# SCH_Cupcake-Hacker-Card_2025-04-10.net
KiCad netlist of a schematic drawn in EasyEDA
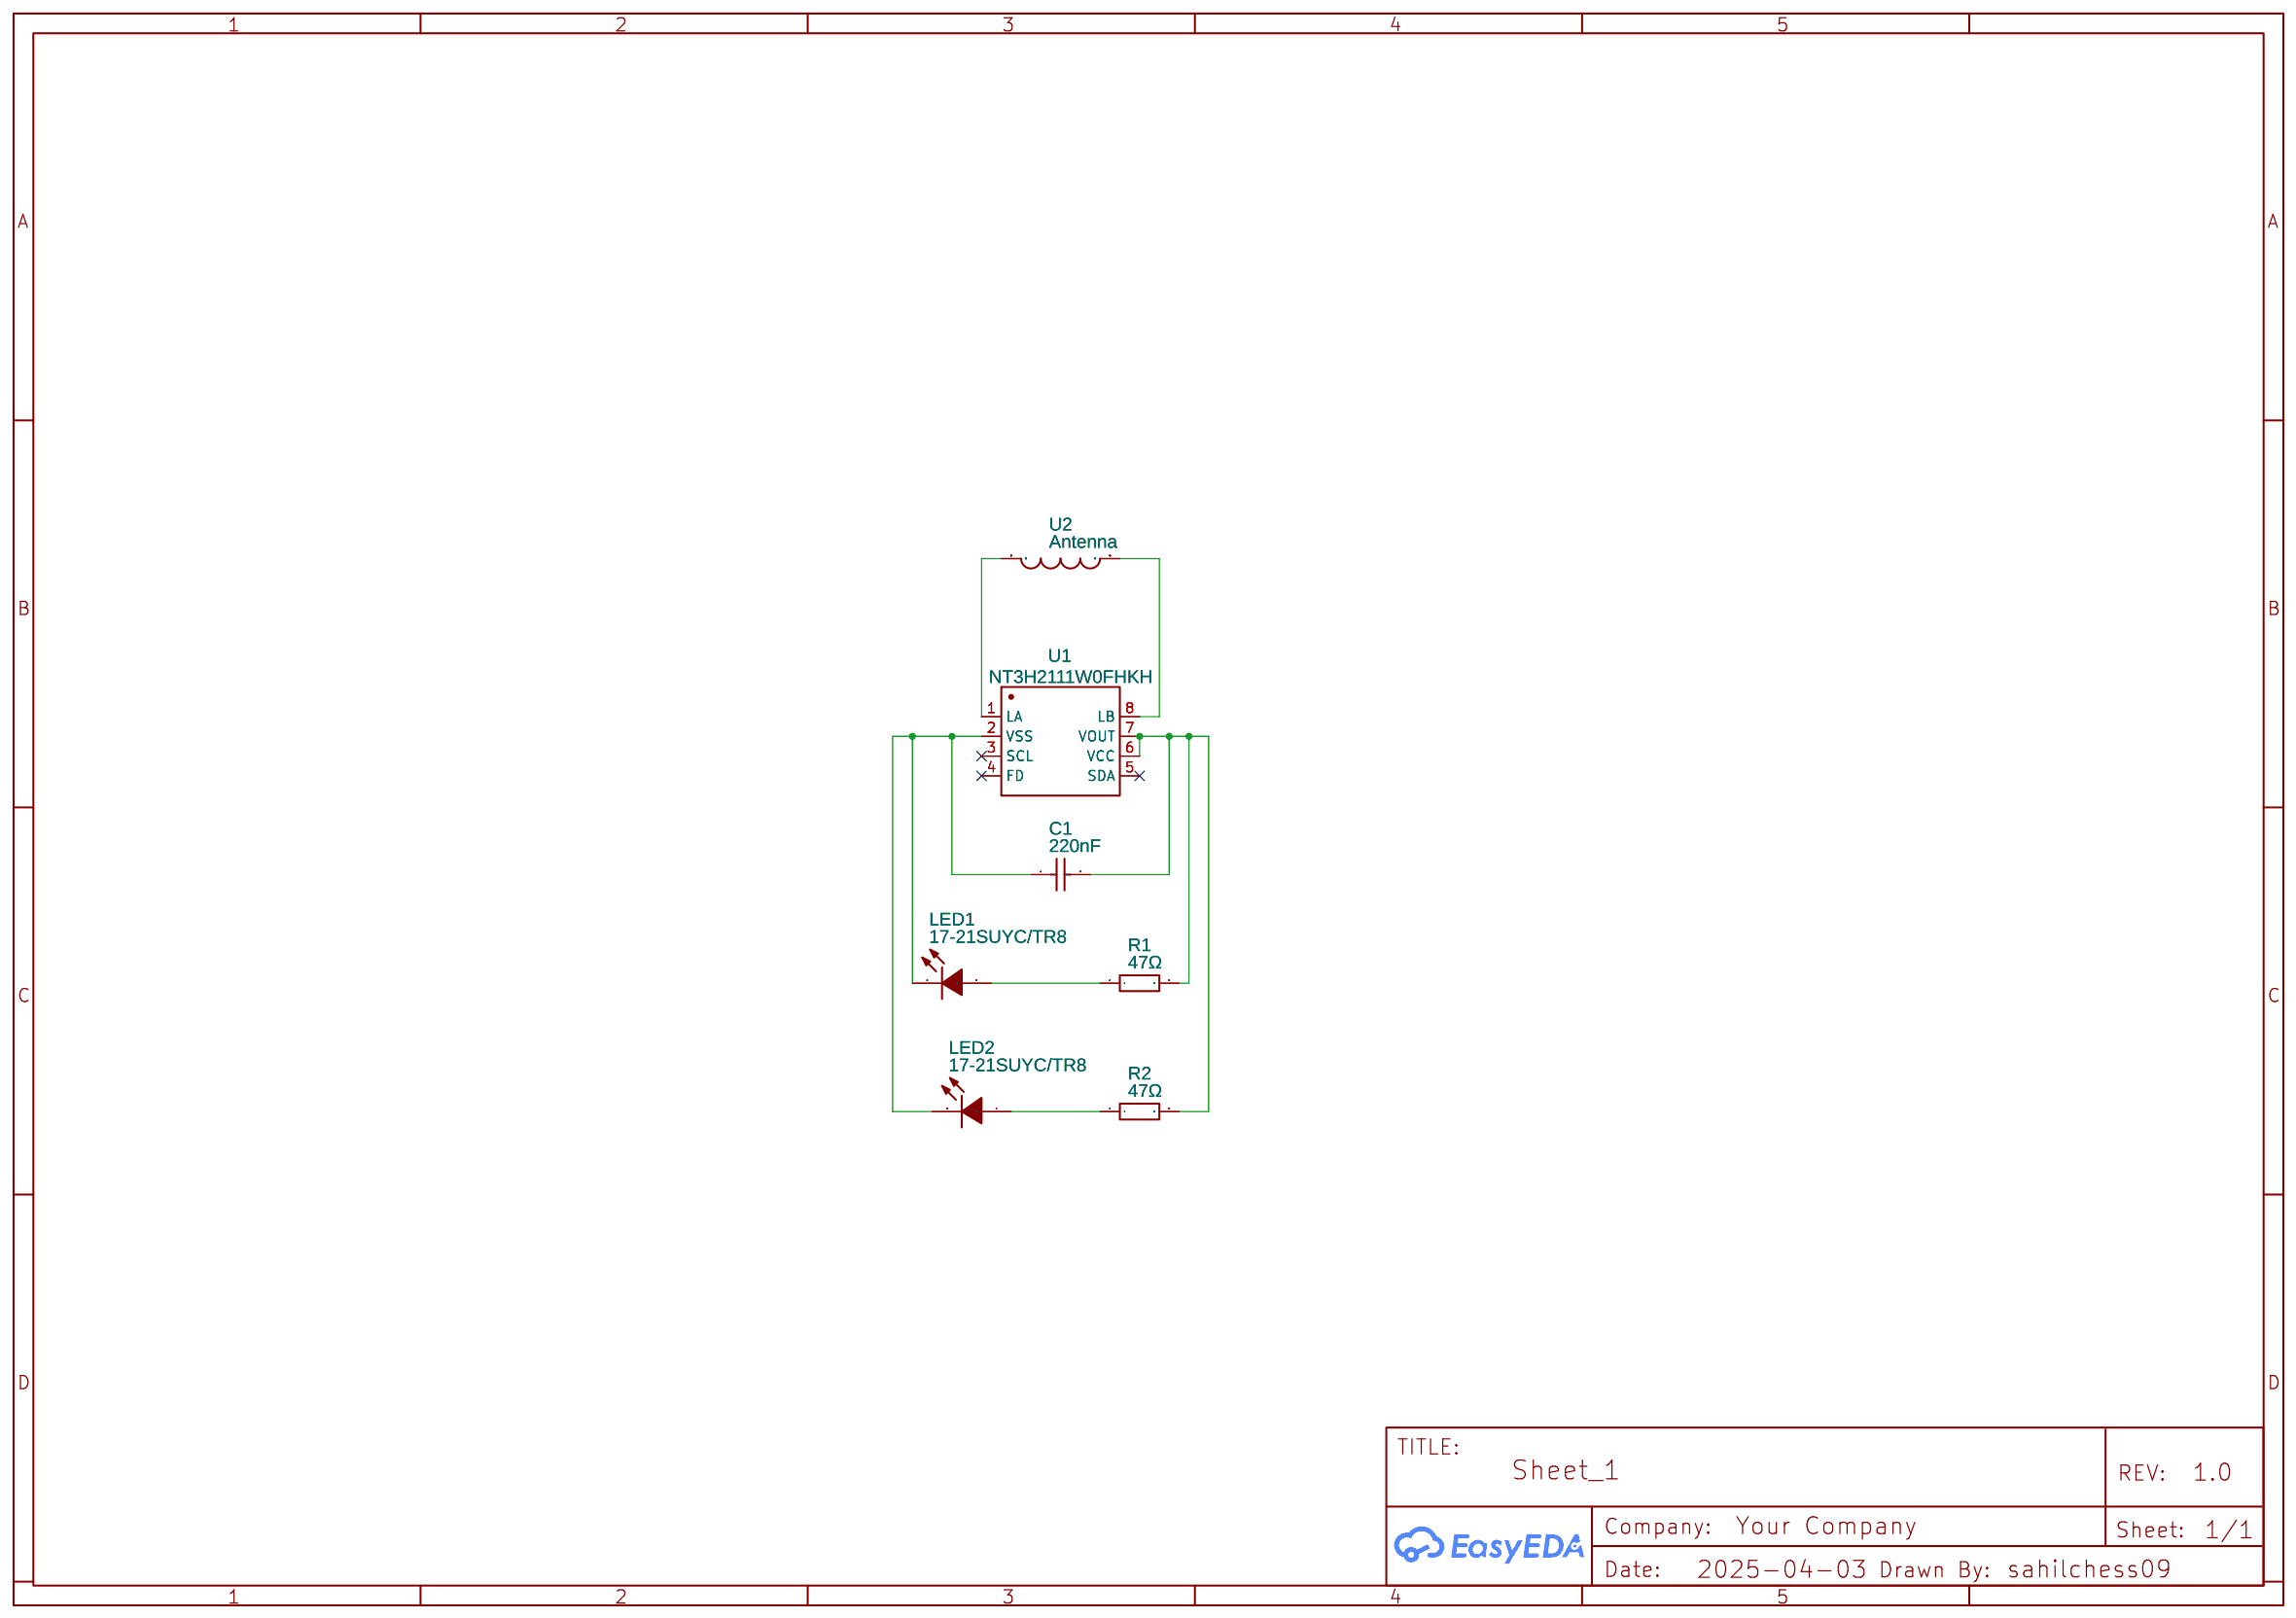
[diagram p0: schematic sheet]

(export (version "E")
  (design (tool "Eeschema 10.0.6"))
  (components
    (comp (ref "C1")
      (value "220nF")
      (fields
        (field (name "Manufacturer Part") "CL10B224KA8NNNC")
        (field (name "Manufacturer") "SAMSUNG(三星)")
      )
      (libsource (lib "") (part "CL10B224KA8NNNC"))
    )
    (comp (ref "LED1")
      (value "17-21SUYC/TR8")
      (fields (field (name "Manufacturer Part") "KT-0805黄灯") (field (name "Manufacturer") "KENTO"))
      (libsource (lib "") (part "17-21SUYC/TR8"))
    )
    (comp (ref "LED2")
      (value "17-21SUYC/TR8")
      (fields (field (name "Manufacturer Part") "KT-0805黄灯") (field (name "Manufacturer") "KENTO"))
      (libsource (lib "") (part "17-21SUYC/TR8"))
    )
    (comp (ref "R1")
      (value "47Ω")
      (fields
        (field (name "Manufacturer Part") "0603WAF470JT5E")
        (field (name "Manufacturer") "UNI-ROYAL(厚声)")
      )
      (libsource (lib "") (part "0603WAF470JT5E"))
    )
    (comp (ref "R2")
      (value "47Ω")
      (fields
        (field (name "Manufacturer Part") "0603WAF470JT5E")
        (field (name "Manufacturer") "UNI-ROYAL(厚声)")
      )
      (libsource (lib "") (part "0603WAF470JT5E"))
    )
    (comp (ref "U1")
      (value "NT3H2111W0FHKH")
      (fields (field (name "Manufacturer") "NXP(恩智浦)"))
      (libsource (lib "") (part "NT3H2111W0FHKH"))
    )
    (comp (ref "U2") (value "Antenna") (libsource (lib "") (part "Antenna")))
  )
  (nets
    (net (code "1") (name "Net-(LED1-+)") (class "Default")
      (node (ref "LED1") (pin "1") (pinfunction "+_1") (pintype "unspecified"))
      (node (ref "R1") (pin "1") (pinfunction "1_1") (pintype "input"))
    )
    (net (code "2") (name "Net-(LED1--)") (class "Default")
      (node (ref "C1") (pin "1") (pinfunction "1_1") (pintype "input"))
      (node (ref "LED1") (pin "2") (pinfunction "-_2") (pintype "unspecified"))
      (node (ref "LED2") (pin "2") (pinfunction "-_2") (pintype "unspecified"))
      (node (ref "U1") (pin "2") (pinfunction "VSS_2") (pintype "unspecified"))
    )
    (net (code "3") (name "Net-(LED2-+)") (class "Default")
      (node (ref "LED2") (pin "1") (pinfunction "+_1") (pintype "unspecified"))
      (node (ref "R2") (pin "1") (pinfunction "1_1") (pintype "input"))
    )
    (net (code "4") (name "Net-(U1-LA)") (class "Default")
      (node (ref "U1") (pin "1") (pinfunction "LA_1") (pintype "unspecified"))
      (node (ref "U2") (pin "P$1") (pinfunction "P$1_P$1") (pintype "unspecified"))
    )
    (net (code "5") (name "Net-(U1-LB)") (class "Default")
      (node (ref "U1") (pin "8") (pinfunction "LB_8") (pintype "unspecified"))
      (node (ref "U2") (pin "P$2") (pinfunction "P$2_P$2") (pintype "unspecified"))
    )
    (net (code "6") (name "Net-(U1-VCC)") (class "Default")
      (node (ref "C1") (pin "2") (pinfunction "2_2") (pintype "input"))
      (node (ref "R1") (pin "2") (pinfunction "2_2") (pintype "input"))
      (node (ref "R2") (pin "2") (pinfunction "2_2") (pintype "input"))
      (node (ref "U1") (pin "6") (pinfunction "VCC_6") (pintype "unspecified"))
      (node (ref "U1") (pin "7") (pinfunction "VOUT_7") (pintype "unspecified"))
    )
    (net (code "7") (name "unconnected-(U1-FD-Pad4)") (class "Default")
      (node (ref "U1") (pin "4") (pinfunction "FD_4") (pintype "unspecified+no_connect"))
    )
    (net (code "8") (name "unconnected-(U1-SCL-Pad3)") (class "Default")
      (node (ref "U1") (pin "3") (pinfunction "SCL_3") (pintype "unspecified+no_connect"))
    )
    (net (code "9") (name "unconnected-(U1-SDA-Pad5)") (class "Default")
      (node (ref "U1") (pin "5") (pinfunction "SDA_5") (pintype "unspecified+no_connect"))
    )
  )
)
